# untitled.net
KiCad netlist of a schematic drawn in EAGLE
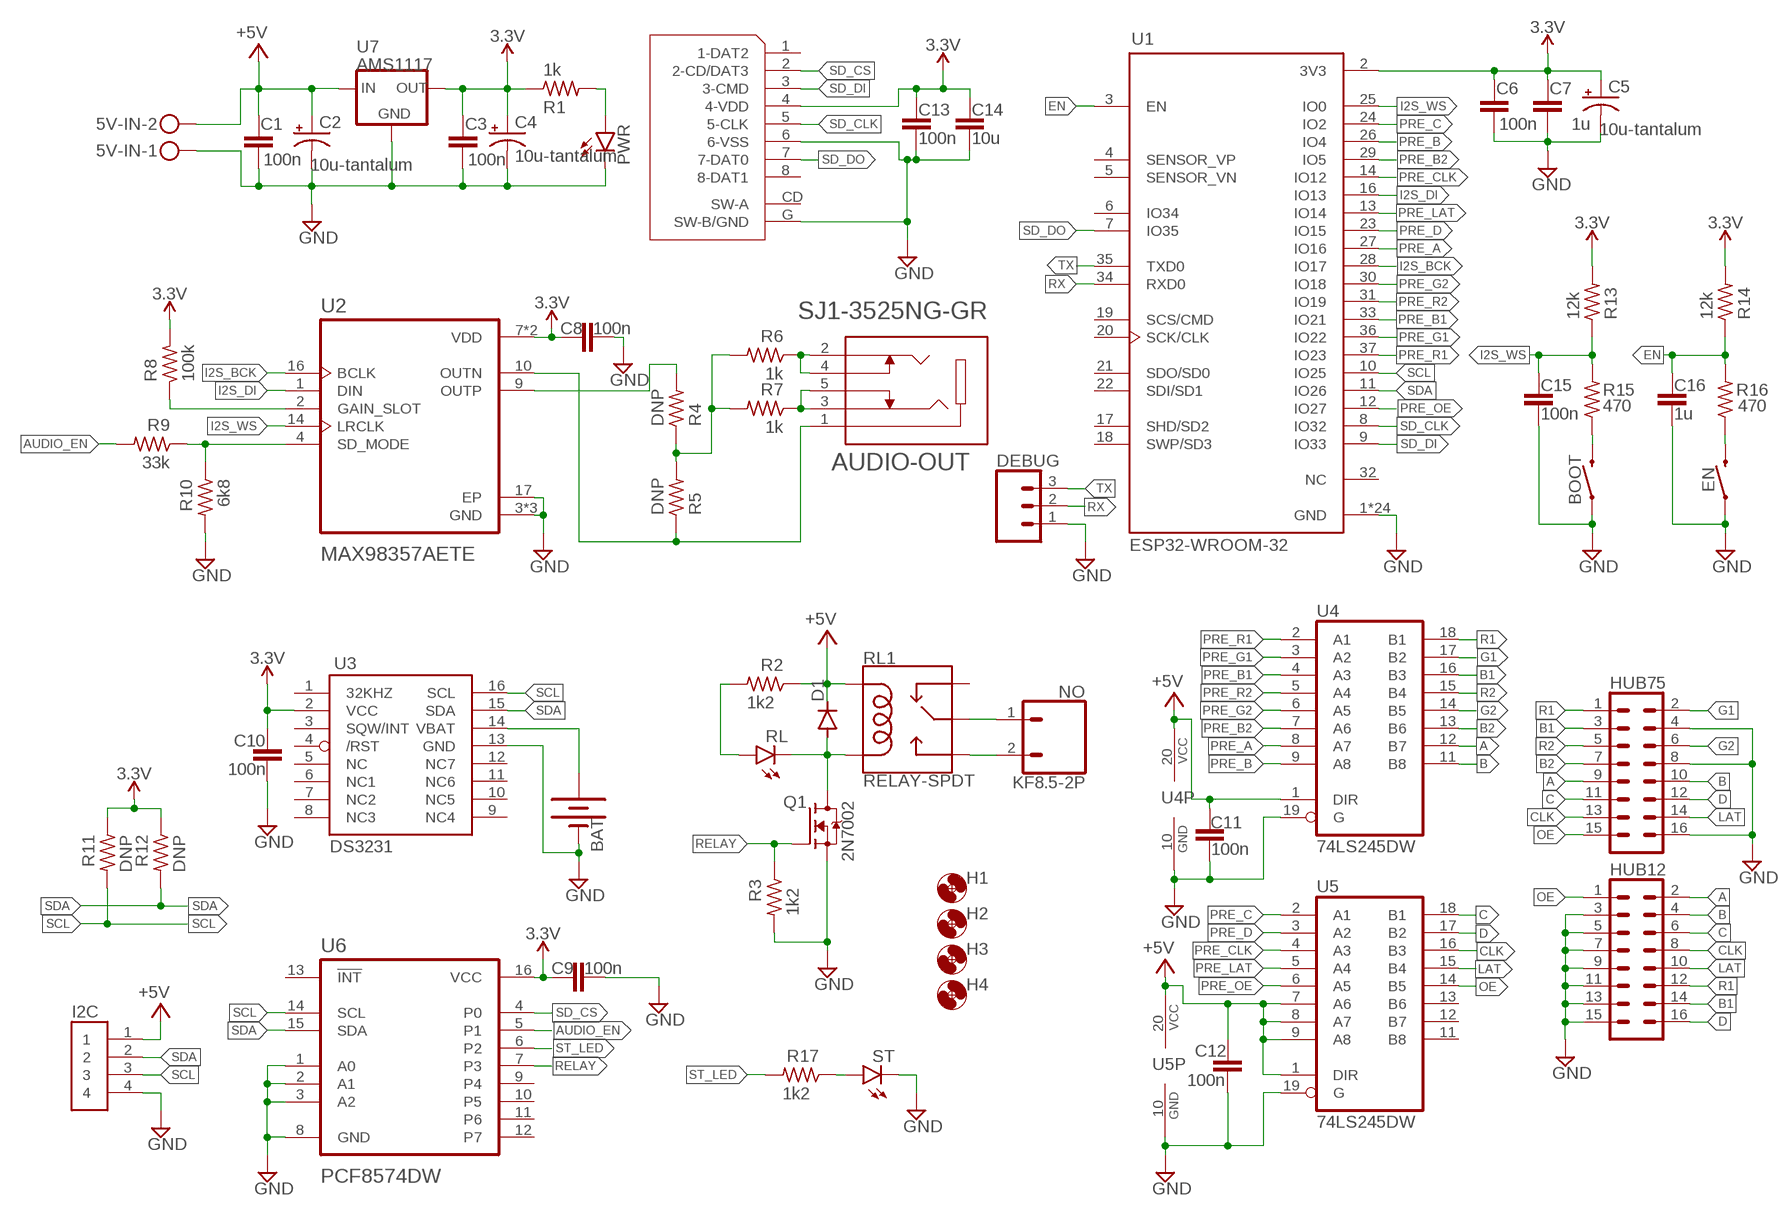
[diagram p0: schematic, sheet 1]

(export (version "E")
  (design (tool "Eeschema 10.0.6"))
  (components
    (comp (ref "5V-IN")
      (value "MKDSN1,5/2-5,08")
      (footprint "eagle-import:MKDSN1,5_2-5,08")
      (libsource (lib "eagle-import") (part "MKDSN1,5/2-5,08"))
    )
    (comp (ref "AUDIO-OUT")
      (value "SJ1-3525NG-GR")
      (footprint "eagle-import:CUI_SJ1-3525NG-GR")
      (fields (field (name "MF") "CUI Devices"))
      (libsource (lib "eagle-import") (part "SJ1-3525NG-GR"))
    )
    (comp (ref "BAT")
      (value "BATTERY-20MM_PTH_KIT")
      (footprint "eagle-import:BATTCOM_20MM_PTH_KIT")
      (libsource (lib "eagle-import") (part "BATTERY-20MM_PTH_KIT"))
    )
    (comp (ref "BOOT")
      (value "MOMENTARY-SWITCH-SPST-SMD-6.0X3.5MM")
      (footprint "eagle-import:TACTILE_SWITCH_SMD_6.0X3.5MM")
      (libsource (lib "eagle-import") (part "MOMENTARY-SWITCH-SPST-SMD-6.0X3.5MM"))
    )
    (comp (ref "C1")
      (value "100n")
      (footprint "eagle-import:C0603K")
      (libsource (lib "eagle-import") (part "C-EUC0603K"))
    )
    (comp (ref "C2")
      (value "10u-tantalum")
      (footprint "eagle-import:CT3528")
      (libsource (lib "eagle-import") (part "CPOL-USCT3528"))
    )
    (comp (ref "C3")
      (value "100n")
      (footprint "eagle-import:C0603K")
      (libsource (lib "eagle-import") (part "C-EUC0603K"))
    )
    (comp (ref "C4")
      (value "10u-tantalum")
      (footprint "eagle-import:CT3528")
      (libsource (lib "eagle-import") (part "CPOL-USCT3528"))
    )
    (comp (ref "C5")
      (value "10u-tantalum")
      (footprint "eagle-import:CT3528")
      (libsource (lib "eagle-import") (part "CPOL-USCT3528"))
    )
    (comp (ref "C6")
      (value "100n")
      (footprint "eagle-import:C0603K")
      (libsource (lib "eagle-import") (part "C-EUC0603K"))
    )
    (comp (ref "C7")
      (value "1u")
      (footprint "eagle-import:C0603K")
      (libsource (lib "eagle-import") (part "C-EUC0603K"))
    )
    (comp (ref "C8")
      (value "100n")
      (footprint "eagle-import:C0603K")
      (libsource (lib "eagle-import") (part "C-EUC0603K"))
    )
    (comp (ref "C9")
      (value "100n")
      (footprint "eagle-import:C0603K")
      (libsource (lib "eagle-import") (part "C-EUC0603K"))
    )
    (comp (ref "C10")
      (value "100n")
      (footprint "eagle-import:C0603K")
      (libsource (lib "eagle-import") (part "C-EUC0603K"))
    )
    (comp (ref "C11")
      (value "100n")
      (footprint "eagle-import:C0603K")
      (libsource (lib "eagle-import") (part "C-EUC0603K"))
    )
    (comp (ref "C12")
      (value "100n")
      (footprint "eagle-import:C0603K")
      (libsource (lib "eagle-import") (part "C-EUC0603K"))
    )
    (comp (ref "C13")
      (value "100n")
      (footprint "eagle-import:C0603K")
      (libsource (lib "eagle-import") (part "C-EUC0603K"))
    )
    (comp (ref "C14")
      (value "10u")
      (footprint "eagle-import:C0603K")
      (libsource (lib "eagle-import") (part "C-EUC0603K"))
    )
    (comp (ref "C15")
      (value "100n")
      (footprint "eagle-import:C0603K")
      (libsource (lib "eagle-import") (part "C-EUC0603K"))
    )
    (comp (ref "C16")
      (value "1u")
      (footprint "eagle-import:C0603K")
      (libsource (lib "eagle-import") (part "C-EUC0603K"))
    )
    (comp (ref "D1")
      (value "DIODE-DO-214AC")
      (footprint "eagle-import:DO-214AC")
      (libsource (lib "eagle-import") (part "DIODE-DO-214AC"))
    )
    (comp (ref "DEBUG")
      (value "CONN_03")
      (footprint "eagle-import:1X03")
      (libsource (lib "eagle-import") (part "CONN_03"))
    )
    (comp (ref "EN")
      (value "MOMENTARY-SWITCH-SPST-SMD-6.0X3.5MM")
      (footprint "eagle-import:TACTILE_SWITCH_SMD_6.0X3.5MM")
      (libsource (lib "eagle-import") (part "MOMENTARY-SWITCH-SPST-SMD-6.0X3.5MM"))
    )
    (comp (ref "H1")
      (value "MOUNT-HOLE3.2")
      (footprint "eagle-import:3,2")
      (libsource (lib "eagle-import") (part "MOUNT-HOLE3.2"))
    )
    (comp (ref "H2")
      (value "MOUNT-HOLE3.2")
      (footprint "eagle-import:3,2")
      (libsource (lib "eagle-import") (part "MOUNT-HOLE3.2"))
    )
    (comp (ref "H3")
      (value "MOUNT-HOLE3.2")
      (footprint "eagle-import:3,2")
      (libsource (lib "eagle-import") (part "MOUNT-HOLE3.2"))
    )
    (comp (ref "H4")
      (value "MOUNT-HOLE3.2")
      (footprint "eagle-import:3,2")
      (libsource (lib "eagle-import") (part "MOUNT-HOLE3.2"))
    )
    (comp (ref "HUB12")
      (value "CONN_08X2_SHROUD")
      (footprint "eagle-import:2X8-SHROUDED_LOCK")
      (libsource (lib "eagle-import") (part "CONN_08X2_SHROUD"))
    )
    (comp (ref "HUB75")
      (value "CONN_08X2_SHROUD")
      (footprint "eagle-import:2X8-SHROUDED_LOCK")
      (fields (field (name "SPICEPREFIX") "X"))
      (libsource (lib "eagle-import") (part "CONN_08X2_SHROUD"))
    )
    (comp (ref "I2C")
      (value "B4B-XH-A(LF)(SN)")
      (footprint "eagle-import:JST_B4B-XH-A(LF)(SN)")
      (fields (field (name "MANUFACTURER") " JST Sales America Inc"))
      (libsource (lib "eagle-import") (part "B4B-XH-A(LF)(SN)"))
    )
    (comp (ref "NO")
      (value "KF8.5-2P")
      (footprint "eagle-import:KF7.62")
      (libsource (lib "eagle-import") (part "KF7.62-2P"))
    )
    (comp (ref "PWR")
      (value "LEDCHIP-LED0805")
      (footprint "eagle-import:CHIP-LED0805")
      (libsource (lib "eagle-import") (part "LEDCHIP-LED0805"))
    )
    (comp (ref "Q1")
      (value "2N7002")
      (footprint "eagle-import:SOT95P240X111-3N")
      (fields (field (name "MF") "ON Semiconductor"))
      (libsource (lib "eagle-import") (part "2N7002"))
    )
    (comp (ref "R1")
      (value "1k")
      (footprint "eagle-import:R0603")
      (libsource (lib "eagle-import") (part "R-US_R0603"))
    )
    (comp (ref "R2")
      (value "1k2")
      (footprint "eagle-import:R0603")
      (libsource (lib "eagle-import") (part "R-US_R0603"))
    )
    (comp (ref "R3")
      (value "1k2")
      (footprint "eagle-import:R0603")
      (libsource (lib "eagle-import") (part "R-US_R0603"))
    )
    (comp (ref "R4")
      (value "DNP")
      (footprint "eagle-import:R0603")
      (libsource (lib "eagle-import") (part "R-US_R0603"))
    )
    (comp (ref "R5")
      (value "DNP")
      (footprint "eagle-import:R0603")
      (libsource (lib "eagle-import") (part "R-US_R0603"))
    )
    (comp (ref "R6")
      (value "1k")
      (footprint "eagle-import:R0603")
      (libsource (lib "eagle-import") (part "R-US_R0603"))
    )
    (comp (ref "R7")
      (value "1k")
      (footprint "eagle-import:R0603")
      (libsource (lib "eagle-import") (part "R-US_R0603"))
    )
    (comp (ref "R8")
      (value "100k")
      (footprint "eagle-import:R0603")
      (libsource (lib "eagle-import") (part "R-US_R0603"))
    )
    (comp (ref "R9")
      (value "33k")
      (footprint "eagle-import:R0603")
      (libsource (lib "eagle-import") (part "R-US_R0603"))
    )
    (comp (ref "R10")
      (value "6k8")
      (footprint "eagle-import:R0603")
      (libsource (lib "eagle-import") (part "R-US_R0603"))
    )
    (comp (ref "R11")
      (value "DNP")
      (footprint "eagle-import:R0603")
      (libsource (lib "eagle-import") (part "R-US_R0603"))
    )
    (comp (ref "R12")
      (value "DNP")
      (footprint "eagle-import:R0603")
      (libsource (lib "eagle-import") (part "R-US_R0603"))
    )
    (comp (ref "R13")
      (value "12k")
      (footprint "eagle-import:R0603")
      (libsource (lib "eagle-import") (part "R-US_R0603"))
    )
    (comp (ref "R14")
      (value "12k")
      (footprint "eagle-import:R0603")
      (libsource (lib "eagle-import") (part "R-US_R0603"))
    )
    (comp (ref "R15")
      (value "470")
      (footprint "eagle-import:R0603")
      (libsource (lib "eagle-import") (part "R-US_R0603"))
    )
    (comp (ref "R16")
      (value "470")
      (footprint "eagle-import:R0603")
      (libsource (lib "eagle-import") (part "R-US_R0603"))
    )
    (comp (ref "R17")
      (value "1k2")
      (footprint "eagle-import:R0603")
      (libsource (lib "eagle-import") (part "R-US_R0603"))
    )
    (comp (ref "RL")
      (value "LEDCHIP-LED0805")
      (footprint "eagle-import:CHIP-LED0805")
      (libsource (lib "eagle-import") (part "LEDCHIP-LED0805"))
    )
    (comp (ref "RL1")
      (value "RELAY-SPDT")
      (footprint "eagle-import:RELAY_G5LE")
      (libsource (lib "eagle-import") (part "RELAY-SPDT"))
    )
    (comp (ref "ST")
      (value "LEDCHIP-LED0805")
      (footprint "eagle-import:CHIP-LED0805")
      (libsource (lib "eagle-import") (part "LEDCHIP-LED0805"))
    )
    (comp (ref "U1")
      (value "ESP32-WROOM-32")
      (footprint "eagle-import:MODULE_ESP32-WROOM-32")
      (fields (field (name "MANUFACTURER") "Espressif Systems"))
      (libsource (lib "eagle-import") (part "ESP32-WROOM-32"))
    )
    (comp (ref "U2")
      (value "MAX98357AETE")
      (footprint "eagle-import:QFN50P300X300X80-17N")
      (fields (field (name "MF") "Maxim Integrated"))
      (libsource (lib "eagle-import") (part "MAX98357AETE"))
    )
    (comp (ref "U3")
      (value "DS3231/SO")
      (footprint "eagle-import:SO16W")
      (libsource (lib "eagle-import") (part "DS3231/SO"))
    )
    (comp (ref "U4")
      (value "74LS245DW")
      (footprint "eagle-import:SO20W")
      (libsource (lib "eagle-import") (part "74245DWLS"))
    )
    (comp (ref "U5")
      (value "74LS245DW")
      (footprint "eagle-import:SO20W")
      (libsource (lib "eagle-import") (part "74245DWLS"))
    )
    (comp (ref "U6")
      (value "PCF8574DW")
      (footprint "eagle-import:SOIC127P1030X265-16N")
      (fields (field (name "MF") "Texas Instruments"))
      (libsource (lib "eagle-import") (part "PCF8574DW"))
    )
    (comp (ref "U7")
      (value "AMS1117")
      (footprint "eagle-import:SOT89R")
      (libsource (lib "eagle-import") (part "AMS1117"))
    )
    (comp (ref "μSD")
      (value "112J-TDAR-R01")
      (footprint "eagle-import:112J-TDAR-R01")
      (libsource (lib "eagle-import") (part "112J-TDAR-R01"))
    )
  )
  (nets
    (net (code "1") (name "+5V") (class "Default")
      (node (ref "5V-IN") (pin "2") (pinfunction "KL_2") (pintype "passive"))
      (node (ref "C1") (pin "1") (pinfunction "1_1") (pintype "passive"))
      (node (ref "C11") (pin "1") (pinfunction "1_1") (pintype "passive"))
      (node (ref "C12") (pin "2") (pinfunction "2_2") (pintype "passive"))
      (node (ref "C2") (pin "+") (pinfunction "+_+") (pintype "passive"))
      (node (ref "D1") (pin "C") (pinfunction "C_C") (pintype "passive"))
      (node (ref "I2C") (pin "1") (pinfunction "1_1") (pintype "passive"))
      (node (ref "R2") (pin "1") (pinfunction "1_1") (pintype "passive"))
      (node (ref "RL1") (pin "2") (pinfunction "COIL1_2") (pintype "bidirectional"))
      (node (ref "U4") (pin "1") (pinfunction "DIR_1") (pintype "input"))
      (node (ref "U4") (pin "20") (pinfunction "VCC_20") (pintype "power_in"))
      (node (ref "U5") (pin "1") (pinfunction "DIR_1") (pintype "input"))
      (node (ref "U5") (pin "20") (pinfunction "VCC_20") (pintype "power_in"))
      (node (ref "U5") (pin "7") (pinfunction "A6_7") (pintype "bidirectional"))
      (node (ref "U5") (pin "8") (pinfunction "A7_8") (pintype "bidirectional"))
      (node (ref "U5") (pin "9") (pinfunction "A8_9") (pintype "bidirectional"))
      (node (ref "U7") (pin "1") (pinfunction "IN_1") (pintype "input"))
    )
    (net (code "2") (name "3.3V") (class "Default")
      (node (ref "C10") (pin "2") (pinfunction "2_2") (pintype "passive"))
      (node (ref "C13") (pin "2") (pinfunction "2_2") (pintype "passive"))
      (node (ref "C14") (pin "2") (pinfunction "2_2") (pintype "passive"))
      (node (ref "C3") (pin "1") (pinfunction "1_1") (pintype "passive"))
      (node (ref "C4") (pin "+") (pinfunction "+_+") (pintype "passive"))
      (node (ref "C5") (pin "+") (pinfunction "+_+") (pintype "passive"))
      (node (ref "C6") (pin "1") (pinfunction "1_1") (pintype "passive"))
      (node (ref "C7") (pin "1") (pinfunction "1_1") (pintype "passive"))
      (node (ref "C8") (pin "1") (pinfunction "1_1") (pintype "passive"))
      (node (ref "C9") (pin "1") (pinfunction "1_1") (pintype "passive"))
      (node (ref "R1") (pin "1") (pinfunction "1_1") (pintype "passive"))
      (node (ref "R11") (pin "1") (pinfunction "1_1") (pintype "passive"))
      (node (ref "R12") (pin "1") (pinfunction "1_1") (pintype "passive"))
      (node (ref "R13") (pin "2") (pinfunction "2_2") (pintype "passive"))
      (node (ref "R14") (pin "2") (pinfunction "2_2") (pintype "passive"))
      (node (ref "R8") (pin "2") (pinfunction "2_2") (pintype "passive"))
      (node (ref "U1") (pin "2") (pinfunction "3V3_2") (pintype "power_in"))
      (node (ref "U2") (pin "7") (pinfunction "VDD_7") (pintype "power_in"))
      (node (ref "U2") (pin "8") (pinfunction "VDD_8") (pintype "power_in"))
      (node (ref "U3") (pin "2") (pinfunction "VCC_2") (pintype "power_in"))
      (node (ref "U6") (pin "16") (pinfunction "VCC_16") (pintype "power_in"))
      (node (ref "U7") (pin "3") (pinfunction "OUT_3") (pintype "passive"))
      (node (ref "U7") (pin "4") (pinfunction "OUT_4") (pintype "passive"))
      (node (ref "μSD") (pin "4") (pinfunction "4-VDD_4") (pintype "bidirectional"))
    )
    (net (code "3") (name "A") (class "Default")
      (node (ref "HUB12") (pin "2") (pinfunction "2_2") (pintype "passive"))
      (node (ref "HUB75") (pin "9") (pinfunction "9_9") (pintype "passive"))
      (node (ref "U4") (pin "12") (pinfunction "B7_12") (pintype "bidirectional"))
    )
    (net (code "4") (name "AUDIO_EN") (class "Default")
      (node (ref "R9") (pin "2") (pinfunction "2_2") (pintype "passive"))
      (node (ref "U6") (pin "5") (pinfunction "P1_5") (pintype "bidirectional"))
    )
    (net (code "5") (name "B") (class "Default")
      (node (ref "HUB12") (pin "4") (pinfunction "4_4") (pintype "passive"))
      (node (ref "HUB75") (pin "10") (pinfunction "10_10") (pintype "passive"))
      (node (ref "U4") (pin "11") (pinfunction "B8_11") (pintype "bidirectional"))
    )
    (net (code "6") (name "B1") (class "Default")
      (node (ref "HUB12") (pin "14") (pinfunction "14_14") (pintype "passive"))
      (node (ref "HUB75") (pin "3") (pinfunction "3_3") (pintype "passive"))
      (node (ref "U4") (pin "16") (pinfunction "B3_16") (pintype "bidirectional"))
    )
    (net (code "7") (name "B2") (class "Default")
      (node (ref "HUB75") (pin "7") (pinfunction "7_7") (pintype "passive"))
      (node (ref "U4") (pin "13") (pinfunction "B6_13") (pintype "bidirectional"))
    )
    (net (code "8") (name "C") (class "Default")
      (node (ref "HUB12") (pin "6") (pinfunction "6_6") (pintype "passive"))
      (node (ref "HUB75") (pin "11") (pinfunction "11_11") (pintype "passive"))
      (node (ref "U5") (pin "18") (pinfunction "B1_18") (pintype "bidirectional"))
    )
    (net (code "9") (name "CLK") (class "Default")
      (node (ref "HUB12") (pin "8") (pinfunction "8_8") (pintype "passive"))
      (node (ref "HUB75") (pin "13") (pinfunction "13_13") (pintype "passive"))
      (node (ref "U5") (pin "16") (pinfunction "B3_16") (pintype "bidirectional"))
    )
    (net (code "10") (name "D") (class "Default")
      (node (ref "HUB12") (pin "16") (pinfunction "16_16") (pintype "passive"))
      (node (ref "HUB75") (pin "12") (pinfunction "12_12") (pintype "passive"))
      (node (ref "U5") (pin "17") (pinfunction "B2_17") (pintype "bidirectional"))
    )
    (net (code "11") (name "EN") (class "Default")
      (node (ref "C16") (pin "2") (pinfunction "2_2") (pintype "passive"))
      (node (ref "R14") (pin "1") (pinfunction "1_1") (pintype "passive"))
      (node (ref "R16") (pin "2") (pinfunction "2_2") (pintype "passive"))
      (node (ref "U1") (pin "3") (pinfunction "EN_3") (pintype "input"))
    )
    (net (code "12") (name "G1") (class "Default")
      (node (ref "HUB75") (pin "2") (pinfunction "2_2") (pintype "passive"))
      (node (ref "U4") (pin "17") (pinfunction "B2_17") (pintype "bidirectional"))
    )
    (net (code "13") (name "G2") (class "Default")
      (node (ref "HUB75") (pin "6") (pinfunction "6_6") (pintype "passive"))
      (node (ref "U4") (pin "14") (pinfunction "B5_14") (pintype "bidirectional"))
    )
    (net (code "14") (name "GND") (class "Default")
      (node (ref "5V-IN") (pin "1") (pinfunction "KL_1") (pintype "passive"))
      (node (ref "BAT") (pin "2") (pinfunction "-_2") (pintype "power_in"))
      (node (ref "BOOT") (pin "1") (pinfunction "1_1") (pintype "passive"))
      (node (ref "C1") (pin "2") (pinfunction "2_2") (pintype "passive"))
      (node (ref "C10") (pin "1") (pinfunction "1_1") (pintype "passive"))
      (node (ref "C11") (pin "2") (pinfunction "2_2") (pintype "passive"))
      (node (ref "C12") (pin "1") (pinfunction "1_1") (pintype "passive"))
      (node (ref "C13") (pin "1") (pinfunction "1_1") (pintype "passive"))
      (node (ref "C14") (pin "1") (pinfunction "1_1") (pintype "passive"))
      (node (ref "C15") (pin "1") (pinfunction "1_1") (pintype "passive"))
      (node (ref "C16") (pin "1") (pinfunction "1_1") (pintype "passive"))
      (node (ref "C2") (pin "-") (pinfunction "-_-") (pintype "passive"))
      (node (ref "C3") (pin "2") (pinfunction "2_2") (pintype "passive"))
      (node (ref "C4") (pin "-") (pinfunction "-_-") (pintype "passive"))
      (node (ref "C5") (pin "-") (pinfunction "-_-") (pintype "passive"))
      (node (ref "C6") (pin "2") (pinfunction "2_2") (pintype "passive"))
      (node (ref "C7") (pin "2") (pinfunction "2_2") (pintype "passive"))
      (node (ref "C8") (pin "2") (pinfunction "2_2") (pintype "passive"))
      (node (ref "C9") (pin "2") (pinfunction "2_2") (pintype "passive"))
      (node (ref "DEBUG") (pin "1") (pinfunction "1_1") (pintype "passive"))
      (node (ref "EN") (pin "1") (pinfunction "1_1") (pintype "passive"))
      (node (ref "HUB12") (pin "11") (pinfunction "11_11") (pintype "passive"))
      (node (ref "HUB12") (pin "13") (pinfunction "13_13") (pintype "passive"))
      (node (ref "HUB12") (pin "15") (pinfunction "15_15") (pintype "passive"))
      (node (ref "HUB12") (pin "3") (pinfunction "3_3") (pintype "passive"))
      (node (ref "HUB12") (pin "5") (pinfunction "5_5") (pintype "passive"))
      (node (ref "HUB12") (pin "7") (pinfunction "7_7") (pintype "passive"))
      (node (ref "HUB12") (pin "9") (pinfunction "9_9") (pintype "passive"))
      (node (ref "HUB75") (pin "16") (pinfunction "16_16") (pintype "passive"))
      (node (ref "HUB75") (pin "4") (pinfunction "4_4") (pintype "passive"))
      (node (ref "HUB75") (pin "8") (pinfunction "8_8") (pintype "passive"))
      (node (ref "I2C") (pin "4") (pinfunction "4_4") (pintype "passive"))
      (node (ref "PWR") (pin "C") (pinfunction "C_C") (pintype "passive"))
      (node (ref "Q1") (pin "2") (pinfunction "S_2") (pintype "passive"))
      (node (ref "R10") (pin "2") (pinfunction "2_2") (pintype "passive"))
      (node (ref "R3") (pin "2") (pinfunction "2_2") (pintype "passive"))
      (node (ref "ST") (pin "C") (pinfunction "C_C") (pintype "passive"))
      (node (ref "U1") (pin "1") (pinfunction "GND_1") (pintype "power_in"))
      (node (ref "U1") (pin "15") (pinfunction "GND_15") (pintype "power_in"))
      (node (ref "U1") (pin "38") (pinfunction "GND_38") (pintype "power_in"))
      (node (ref "U1") (pin "39_1") (pinfunction "GND_39_1") (pintype "power_in"))
      (node (ref "U1") (pin "39_10") (pinfunction "GND_39_10") (pintype "power_in"))
      (node (ref "U1") (pin "39_11") (pinfunction "GND_39_11") (pintype "power_in"))
      (node (ref "U1") (pin "39_12") (pinfunction "GND_39_12") (pintype "power_in"))
      (node (ref "U1") (pin "39_13") (pinfunction "GND_39_13") (pintype "power_in"))
      (node (ref "U1") (pin "39_14") (pinfunction "GND_39_14") (pintype "power_in"))
      (node (ref "U1") (pin "39_15") (pinfunction "GND_39_15") (pintype "power_in"))
      (node (ref "U1") (pin "39_16") (pinfunction "GND_39_16") (pintype "power_in"))
      (node (ref "U1") (pin "39_17") (pinfunction "GND_39_17") (pintype "power_in"))
      (node (ref "U1") (pin "39_18") (pinfunction "GND_39_18") (pintype "power_in"))
      (node (ref "U1") (pin "39_19") (pinfunction "GND_39_19") (pintype "power_in"))
      (node (ref "U1") (pin "39_2") (pinfunction "GND_39_2") (pintype "power_in"))
      (node (ref "U1") (pin "39_20") (pinfunction "GND_39_20") (pintype "power_in"))
      (node (ref "U1") (pin "39_21") (pinfunction "GND_39_21") (pintype "power_in"))
      (node (ref "U1") (pin "39_3") (pinfunction "GND_39_3") (pintype "power_in"))
      (node (ref "U1") (pin "39_4") (pinfunction "GND_39_4") (pintype "power_in"))
      (node (ref "U1") (pin "39_5") (pinfunction "GND_39_5") (pintype "power_in"))
      (node (ref "U1") (pin "39_6") (pinfunction "GND_39_6") (pintype "power_in"))
      (node (ref "U1") (pin "39_7") (pinfunction "GND_39_7") (pintype "power_in"))
      (node (ref "U1") (pin "39_8") (pinfunction "GND_39_8") (pintype "power_in"))
      (node (ref "U1") (pin "39_9") (pinfunction "GND_39_9") (pintype "power_in"))
      (node (ref "U2") (pin "11") (pinfunction "GND_11") (pintype "power_in"))
      (node (ref "U2") (pin "15") (pinfunction "GND_15") (pintype "power_in"))
      (node (ref "U2") (pin "17") (pinfunction "EP_17") (pintype "power_in"))
      (node (ref "U2") (pin "3") (pinfunction "GND_3") (pintype "power_in"))
      (node (ref "U3") (pin "13") (pinfunction "GND_13") (pintype "power_in"))
      (node (ref "U4") (pin "10") (pinfunction "GND_10") (pintype "power_in"))
      (node (ref "U4") (pin "19") (pinfunction "G_19") (pintype "input"))
      (node (ref "U5") (pin "10") (pinfunction "GND_10") (pintype "power_in"))
      (node (ref "U5") (pin "19") (pinfunction "G_19") (pintype "input"))
      (node (ref "U6") (pin "1") (pinfunction "A0_1") (pintype "input"))
      (node (ref "U6") (pin "2") (pinfunction "A1_2") (pintype "input"))
      (node (ref "U6") (pin "3") (pinfunction "A2_3") (pintype "input"))
      (node (ref "U6") (pin "8") (pinfunction "GND_8") (pintype "power_in"))
      (node (ref "U7") (pin "2") (pinfunction "GND_2") (pintype "input"))
      (node (ref "μSD") (pin "6") (pinfunction "6-VSS_6") (pintype "bidirectional"))
      (node (ref "μSD") (pin "G") (pinfunction "SW-B/GND_G") (pintype "bidirectional"))
    )
    (net (code "15") (name "I2S_BCK") (class "Default")
      (node (ref "U1") (pin "28") (pinfunction "IO17_28") (pintype "bidirectional"))
      (node (ref "U2") (pin "16") (pinfunction "BCLK_16") (pintype "input"))
    )
    (net (code "16") (name "I2S_DI") (class "Default")
      (node (ref "U1") (pin "16") (pinfunction "IO13_16") (pintype "bidirectional"))
      (node (ref "U2") (pin "1") (pinfunction "DIN_1") (pintype "input"))
    )
    (net (code "17") (name "I2S_WS") (class "Default")
      (node (ref "C15") (pin "2") (pinfunction "2_2") (pintype "passive"))
      (node (ref "R13") (pin "1") (pinfunction "1_1") (pintype "passive"))
      (node (ref "R15") (pin "2") (pinfunction "2_2") (pintype "passive"))
      (node (ref "U1") (pin "25") (pinfunction "IO0_25") (pintype "bidirectional"))
      (node (ref "U2") (pin "14") (pinfunction "LRCLK_14") (pintype "input"))
    )
    (net (code "18") (name "LAT") (class "Default")
      (node (ref "HUB12") (pin "10") (pinfunction "10_10") (pintype "passive"))
      (node (ref "HUB75") (pin "14") (pinfunction "14_14") (pintype "passive"))
      (node (ref "U5") (pin "15") (pinfunction "B4_15") (pintype "bidirectional"))
    )
    (net (code "19") (name "Net-(AUDIO-OUT-Pad2)") (class "Default")
      (node (ref "AUDIO-OUT") (pin "2") (pinfunction "2_2") (pintype "passive"))
      (node (ref "AUDIO-OUT") (pin "4") (pinfunction "4_4") (pintype "passive"))
      (node (ref "R6") (pin "1") (pinfunction "1_1") (pintype "passive"))
    )
    (net (code "20") (name "Net-(AUDIO-OUT-Pad3)") (class "Default")
      (node (ref "AUDIO-OUT") (pin "3") (pinfunction "3_3") (pintype "passive"))
      (node (ref "AUDIO-OUT") (pin "5") (pinfunction "5_5") (pintype "passive"))
      (node (ref "R7") (pin "1") (pinfunction "1_1") (pintype "passive"))
    )
    (net (code "21") (name "Net-(BAT-+)") (class "Default")
      (node (ref "BAT") (pin "1") (pinfunction "+_1") (pintype "power_in"))
      (node (ref "U3") (pin "14") (pinfunction "VBAT_14") (pintype "power_in"))
    )
    (net (code "22") (name "Net-(BOOT-Pad2)") (class "Default")
      (node (ref "BOOT") (pin "2") (pinfunction "2_2") (pintype "passive"))
      (node (ref "R15") (pin "1") (pinfunction "1_1") (pintype "passive"))
    )
    (net (code "23") (name "Net-(EN-Pad2)") (class "Default")
      (node (ref "EN") (pin "2") (pinfunction "2_2") (pintype "passive"))
      (node (ref "R16") (pin "1") (pinfunction "1_1") (pintype "passive"))
    )
    (net (code "24") (name "Net-(PWR-PadA)") (class "Default")
      (node (ref "PWR") (pin "A") (pinfunction "A_A") (pintype "passive"))
      (node (ref "R1") (pin "2") (pinfunction "2_2") (pintype "passive"))
    )
    (net (code "25") (name "Net-(Q1-D)") (class "Default")
      (node (ref "D1") (pin "A") (pinfunction "A_A") (pintype "passive"))
      (node (ref "Q1") (pin "3") (pinfunction "D_3") (pintype "passive"))
      (node (ref "RL") (pin "C") (pinfunction "C_C") (pintype "passive"))
      (node (ref "RL1") (pin "5") (pinfunction "COIL2_5") (pintype "bidirectional"))
    )
    (net (code "26") (name "Net-(R2-Pad2)") (class "Default")
      (node (ref "R2") (pin "2") (pinfunction "2_2") (pintype "passive"))
      (node (ref "RL") (pin "A") (pinfunction "A_A") (pintype "passive"))
    )
    (net (code "27") (name "Net-(R4-Pad1)") (class "Default")
      (node (ref "R4") (pin "1") (pinfunction "1_1") (pintype "passive"))
      (node (ref "R5") (pin "2") (pinfunction "2_2") (pintype "passive"))
      (node (ref "R6") (pin "2") (pinfunction "2_2") (pintype "passive"))
      (node (ref "R7") (pin "2") (pinfunction "2_2") (pintype "passive"))
    )
    (net (code "28") (name "Net-(R17-Pad1)") (class "Default")
      (node (ref "R17") (pin "1") (pinfunction "1_1") (pintype "passive"))
      (node (ref "ST") (pin "A") (pinfunction "A_A") (pintype "passive"))
    )
    (net (code "29") (name "Net-(RL1-MAIN)") (class "Default")
      (node (ref "NO") (pin "1") (pinfunction "1_1") (pintype "passive"))
      (node (ref "RL1") (pin "1") (pinfunction "MAIN_1") (pintype "bidirectional"))
    )
    (net (code "30") (name "Net-(RL1-NO)") (class "Default")
      (node (ref "NO") (pin "2") (pinfunction "2_2") (pintype "passive"))
      (node (ref "RL1") (pin "3") (pinfunction "NO_3") (pintype "bidirectional"))
    )
    (net (code "31") (name "Net-(U2-GAIN_SLOT)") (class "Default")
      (node (ref "R8") (pin "1") (pinfunction "1_1") (pintype "passive"))
      (node (ref "U2") (pin "2") (pinfunction "GAIN_SLOT_2") (pintype "input"))
    )
    (net (code "32") (name "Net-(U2-OUTN)") (class "Default")
      (node (ref "AUDIO-OUT") (pin "1") (pinfunction "1_1") (pintype "passive"))
      (node (ref "R5") (pin "1") (pinfunction "1_1") (pintype "passive"))
      (node (ref "U2") (pin "10") (pinfunction "OUTN_10") (pintype "output"))
    )
    (net (code "33") (name "Net-(U2-OUTP)") (class "Default")
      (node (ref "R4") (pin "2") (pinfunction "2_2") (pintype "passive"))
      (node (ref "U2") (pin "9") (pinfunction "OUTP_9") (pintype "output"))
    )
    (net (code "34") (name "Net-(U2-SD_MODE)") (class "Default")
      (node (ref "R10") (pin "1") (pinfunction "1_1") (pintype "passive"))
      (node (ref "R9") (pin "1") (pinfunction "1_1") (pintype "passive"))
      (node (ref "U2") (pin "4") (pinfunction "SD_MODE_4") (pintype "input"))
    )
    (net (code "35") (name "OE") (class "Default")
      (node (ref "HUB12") (pin "1") (pinfunction "1_1") (pintype "passive"))
      (node (ref "HUB75") (pin "15") (pinfunction "15_15") (pintype "passive"))
      (node (ref "U5") (pin "14") (pinfunction "B5_14") (pintype "bidirectional"))
    )
    (net (code "36") (name "PRE_A") (class "Default")
      (node (ref "U1") (pin "27") (pinfunction "IO16_27") (pintype "bidirectional"))
      (node (ref "U4") (pin "8") (pinfunction "A7_8") (pintype "bidirectional"))
    )
    (net (code "37") (name "PRE_B") (class "Default")
      (node (ref "U1") (pin "26") (pinfunction "IO4_26") (pintype "bidirectional"))
      (node (ref "U4") (pin "9") (pinfunction "A8_9") (pintype "bidirectional"))
    )
    (net (code "38") (name "PRE_B1") (class "Default")
      (node (ref "U1") (pin "33") (pinfunction "IO21_33") (pintype "bidirectional"))
      (node (ref "U4") (pin "4") (pinfunction "A3_4") (pintype "bidirectional"))
    )
    (net (code "39") (name "PRE_B2") (class "Default")
      (node (ref "U1") (pin "29") (pinfunction "IO5_29") (pintype "bidirectional"))
      (node (ref "U4") (pin "7") (pinfunction "A6_7") (pintype "bidirectional"))
    )
    (net (code "40") (name "PRE_C") (class "Default")
      (node (ref "U1") (pin "24") (pinfunction "IO2_24") (pintype "bidirectional"))
      (node (ref "U5") (pin "2") (pinfunction "A1_2") (pintype "bidirectional"))
    )
    (net (code "41") (name "PRE_CLK") (class "Default")
      (node (ref "U1") (pin "14") (pinfunction "IO12_14") (pintype "bidirectional"))
      (node (ref "U5") (pin "4") (pinfunction "A3_4") (pintype "bidirectional"))
    )
    (net (code "42") (name "PRE_D") (class "Default")
      (node (ref "U1") (pin "23") (pinfunction "IO15_23") (pintype "bidirectional"))
      (node (ref "U5") (pin "3") (pinfunction "A2_3") (pintype "bidirectional"))
    )
    (net (code "43") (name "PRE_G1") (class "Default")
      (node (ref "U1") (pin "36") (pinfunction "IO22_36") (pintype "bidirectional"))
      (node (ref "U4") (pin "3") (pinfunction "A2_3") (pintype "bidirectional"))
    )
    (net (code "44") (name "PRE_G2") (class "Default")
      (node (ref "U1") (pin "30") (pinfunction "IO18_30") (pintype "bidirectional"))
      (node (ref "U4") (pin "6") (pinfunction "A5_6") (pintype "bidirectional"))
    )
    (net (code "45") (name "PRE_LAT") (class "Default")
      (node (ref "U1") (pin "13") (pinfunction "IO14_13") (pintype "bidirectional"))
      (node (ref "U5") (pin "5") (pinfunction "A4_5") (pintype "bidirectional"))
    )
    (net (code "46") (name "PRE_OE") (class "Default")
      (node (ref "U1") (pin "12") (pinfunction "IO27_12") (pintype "bidirectional"))
      (node (ref "U5") (pin "6") (pinfunction "A5_6") (pintype "bidirectional"))
    )
    (net (code "47") (name "PRE_R1") (class "Default")
      (node (ref "U1") (pin "37") (pinfunction "IO23_37") (pintype "bidirectional"))
      (node (ref "U4") (pin "2") (pinfunction "A1_2") (pintype "bidirectional"))
    )
    (net (code "48") (name "PRE_R2") (class "Default")
      (node (ref "U1") (pin "31") (pinfunction "IO19_31") (pintype "bidirectional"))
      (node (ref "U4") (pin "5") (pinfunction "A4_5") (pintype "bidirectional"))
    )
    (net (code "49") (name "R1") (class "Default")
      (node (ref "HUB12") (pin "12") (pinfunction "12_12") (pintype "passive"))
      (node (ref "HUB75") (pin "1") (pinfunction "1_1") (pintype "passive"))
      (node (ref "U4") (pin "18") (pinfunction "B1_18") (pintype "bidirectional"))
    )
    (net (code "50") (name "R2") (class "Default")
      (node (ref "HUB75") (pin "5") (pinfunction "5_5") (pintype "passive"))
      (node (ref "U4") (pin "15") (pinfunction "B4_15") (pintype "bidirectional"))
    )
    (net (code "51") (name "RELAY") (class "Default")
      (node (ref "Q1") (pin "1") (pinfunction "G_1") (pintype "passive"))
      (node (ref "R3") (pin "1") (pinfunction "1_1") (pintype "passive"))
      (node (ref "U6") (pin "7") (pinfunction "P3_7") (pintype "bidirectional"))
    )
    (net (code "52") (name "RX") (class "Default")
      (node (ref "DEBUG") (pin "2") (pinfunction "2_2") (pintype "passive"))
      (node (ref "U1") (pin "34") (pinfunction "RXD0_34") (pintype "bidirectional"))
    )
    (net (code "53") (name "SCL") (class "Default")
      (node (ref "I2C") (pin "3") (pinfunction "3_3") (pintype "passive"))
      (node (ref "R11") (pin "2") (pinfunction "2_2") (pintype "passive"))
      (node (ref "U1") (pin "10") (pinfunction "IO25_10") (pintype "bidirectional"))
      (node (ref "U3") (pin "16") (pinfunction "SCL_16") (pintype "bidirectional"))
      (node (ref "U6") (pin "14") (pinfunction "SCL_14") (pintype "input"))
    )
    (net (code "54") (name "SDA") (class "Default")
      (node (ref "I2C") (pin "2") (pinfunction "2_2") (pintype "passive"))
      (node (ref "R12") (pin "2") (pinfunction "2_2") (pintype "passive"))
      (node (ref "U1") (pin "11") (pinfunction "IO26_11") (pintype "bidirectional"))
      (node (ref "U3") (pin "15") (pinfunction "SDA_15") (pintype "bidirectional"))
      (node (ref "U6") (pin "15") (pinfunction "SDA_15") (pintype "bidirectional"))
    )
    (net (code "55") (name "SD_CLK") (class "Default")
      (node (ref "U1") (pin "8") (pinfunction "IO32_8") (pintype "bidirectional"))
      (node (ref "μSD") (pin "5") (pinfunction "5-CLK_5") (pintype "bidirectional"))
    )
    (net (code "56") (name "SD_CS") (class "Default")
      (node (ref "U6") (pin "4") (pinfunction "P0_4") (pintype "bidirectional"))
      (node (ref "μSD") (pin "2") (pinfunction "2-CD/DAT3_2") (pintype "bidirectional"))
    )
    (net (code "57") (name "SD_DI") (class "Default")
      (node (ref "U1") (pin "9") (pinfunction "IO33_9") (pintype "bidirectional"))
      (node (ref "μSD") (pin "3") (pinfunction "3-CMD_3") (pintype "bidirectional"))
    )
    (net (code "58") (name "SD_DO") (class "Default")
      (node (ref "U1") (pin "7") (pinfunction "IO35_7") (pintype "input"))
      (node (ref "μSD") (pin "7") (pinfunction "7-DAT0_7") (pintype "bidirectional"))
    )
    (net (code "59") (name "ST_LED") (class "Default")
      (node (ref "R17") (pin "2") (pinfunction "2_2") (pintype "passive"))
      (node (ref "U6") (pin "6") (pinfunction "P2_6") (pintype "bidirectional"))
    )
    (net (code "60") (name "TX") (class "Default")
      (node (ref "DEBUG") (pin "3") (pinfunction "3_3") (pintype "passive"))
      (node (ref "U1") (pin "35") (pinfunction "TXD0_35") (pintype "bidirectional"))
    )
    (net (code "61") (name "unconnected-(RL1-NC-Pad4)") (class "Default")
      (node (ref "RL1") (pin "4") (pinfunction "NC_4") (pintype "bidirectional"))
    )
    (net (code "62") (name "unconnected-(U1-IO34-Pad6)") (class "Default")
      (node (ref "U1") (pin "6") (pinfunction "IO34_6") (pintype "input"))
    )
    (net (code "63") (name "unconnected-(U1-NC-Pad32)") (class "Default")
      (node (ref "U1") (pin "32") (pinfunction "NC_32") (pintype "no_connect"))
    )
    (net (code "64") (name "unconnected-(U1-SCK{slash}CLK-Pad20)") (class "Default")
      (node (ref "U1") (pin "20") (pinfunction "SCK/CLK_20") (pintype "bidirectional"))
    )
    (net (code "65") (name "unconnected-(U1-SCS{slash}CMD-Pad19)") (class "Default")
      (node (ref "U1") (pin "19") (pinfunction "SCS/CMD_19") (pintype "bidirectional"))
    )
    (net (code "66") (name "unconnected-(U1-SDI{slash}SD1-Pad22)") (class "Default")
      (node (ref "U1") (pin "22") (pinfunction "SDI/SD1_22") (pintype "bidirectional"))
    )
    (net (code "67") (name "unconnected-(U1-SDO{slash}SD0-Pad21)") (class "Default")
      (node (ref "U1") (pin "21") (pinfunction "SDO/SD0_21") (pintype "bidirectional"))
    )
    (net (code "68") (name "unconnected-(U1-SENSOR_VN-Pad5)") (class "Default")
      (node (ref "U1") (pin "5") (pinfunction "SENSOR_VN_5") (pintype "input"))
    )
    (net (code "69") (name "unconnected-(U1-SENSOR_VP-Pad4)") (class "Default")
      (node (ref "U1") (pin "4") (pinfunction "SENSOR_VP_4") (pintype "input"))
    )
    (net (code "70") (name "unconnected-(U1-SHD{slash}SD2-Pad17)") (class "Default")
      (node (ref "U1") (pin "17") (pinfunction "SHD/SD2_17") (pintype "bidirectional"))
    )
    (net (code "71") (name "unconnected-(U1-SWP{slash}SD3-Pad18)") (class "Default")
      (node (ref "U1") (pin "18") (pinfunction "SWP/SD3_18") (pintype "bidirectional"))
    )
    (net (code "72") (name "unconnected-(U3-32KHZ-Pad1)") (class "Default")
      (node (ref "U3") (pin "1") (pinfunction "32KHZ_1") (pintype "output"))
    )
    (net (code "73") (name "unconnected-(U3-NC-Pad5)") (class "Default")
      (node (ref "U3") (pin "5") (pinfunction "NC_5") (pintype "no_connect"))
    )
    (net (code "74") (name "unconnected-(U3-NC1-Pad6)") (class "Default")
      (node (ref "U3") (pin "6") (pinfunction "NC1_6") (pintype "no_connect"))
    )
    (net (code "75") (name "unconnected-(U3-NC2-Pad7)") (class "Default")
      (node (ref "U3") (pin "7") (pinfunction "NC2_7") (pintype "no_connect"))
    )
    (net (code "76") (name "unconnected-(U3-NC3-Pad8)") (class "Default")
      (node (ref "U3") (pin "8") (pinfunction "NC3_8") (pintype "no_connect"))
    )
    (net (code "77") (name "unconnected-(U3-NC4-Pad9)") (class "Default")
      (node (ref "U3") (pin "9") (pinfunction "NC4_9") (pintype "no_connect"))
    )
    (net (code "78") (name "unconnected-(U3-NC5-Pad10)") (class "Default")
      (node (ref "U3") (pin "10") (pinfunction "NC5_10") (pintype "no_connect"))
    )
    (net (code "79") (name "unconnected-(U3-NC6-Pad11)") (class "Default")
      (node (ref "U3") (pin "11") (pinfunction "NC6_11") (pintype "no_connect"))
    )
    (net (code "80") (name "unconnected-(U3-NC7-Pad12)") (class "Default")
      (node (ref "U3") (pin "12") (pinfunction "NC7_12") (pintype "no_connect"))
    )
    (net (code "81") (name "unconnected-(U3-SQW{slash}INT-Pad3)") (class "Default")
      (node (ref "U3") (pin "3") (pinfunction "SQW/INT_3") (pintype "output"))
    )
    (net (code "82") (name "unconnected-(U3-{slash}RST-Pad4)") (class "Default")
      (node (ref "U3") (pin "4") (pinfunction "/RST_4") (pintype "passive"))
    )
    (net (code "83") (name "unconnected-(U5A-B6-Pad13)") (class "Default")
      (node (ref "U5") (pin "13") (pinfunction "B6_13") (pintype "bidirectional"))
    )
    (net (code "84") (name "unconnected-(U5A-B7-Pad12)") (class "Default")
      (node (ref "U5") (pin "12") (pinfunction "B7_12") (pintype "bidirectional"))
    )
    (net (code "85") (name "unconnected-(U5A-B8-Pad11)") (class "Default")
      (node (ref "U5") (pin "11") (pinfunction "B8_11") (pintype "bidirectional"))
    )
    (net (code "86") (name "unconnected-(U6-P4-Pad9)") (class "Default")
      (node (ref "U6") (pin "9") (pinfunction "P4_9") (pintype "bidirectional"))
    )
    (net (code "87") (name "unconnected-(U6-P5-Pad10)") (class "Default")
      (node (ref "U6") (pin "10") (pinfunction "P5_10") (pintype "bidirectional"))
    )
    (net (code "88") (name "unconnected-(U6-P6-Pad11)") (class "Default")
      (node (ref "U6") (pin "11") (pinfunction "P6_11") (pintype "bidirectional"))
    )
    (net (code "89") (name "unconnected-(U6-P7-Pad12)") (class "Default")
      (node (ref "U6") (pin "12") (pinfunction "P7_12") (pintype "bidirectional"))
    )
    (net (code "90") (name "unconnected-(U6-~{INT}-Pad13)") (class "Default")
      (node (ref "U6") (pin "13") (pinfunction "~{INT}_13") (pintype "input"))
    )
    (net (code "91") (name "unconnected-(μSD-1-DAT2-Pad1)") (class "Default")
      (node (ref "μSD") (pin "1") (pinfunction "1-DAT2_1") (pintype "bidirectional"))
    )
    (net (code "92") (name "unconnected-(μSD-8-DAT1-Pad8)") (class "Default")
      (node (ref "μSD") (pin "8") (pinfunction "8-DAT1_8") (pintype "bidirectional"))
    )
    (net (code "93") (name "unconnected-(μSD-SW-A-PadCD)") (class "Default")
      (node (ref "μSD") (pin "CD") (pinfunction "SW-A_CD") (pintype "bidirectional"))
    )
  )
)
